# ICS40300-preamp-surfacemount_Rev-D.net
KiCad netlist of a schematic drawn in EAGLE
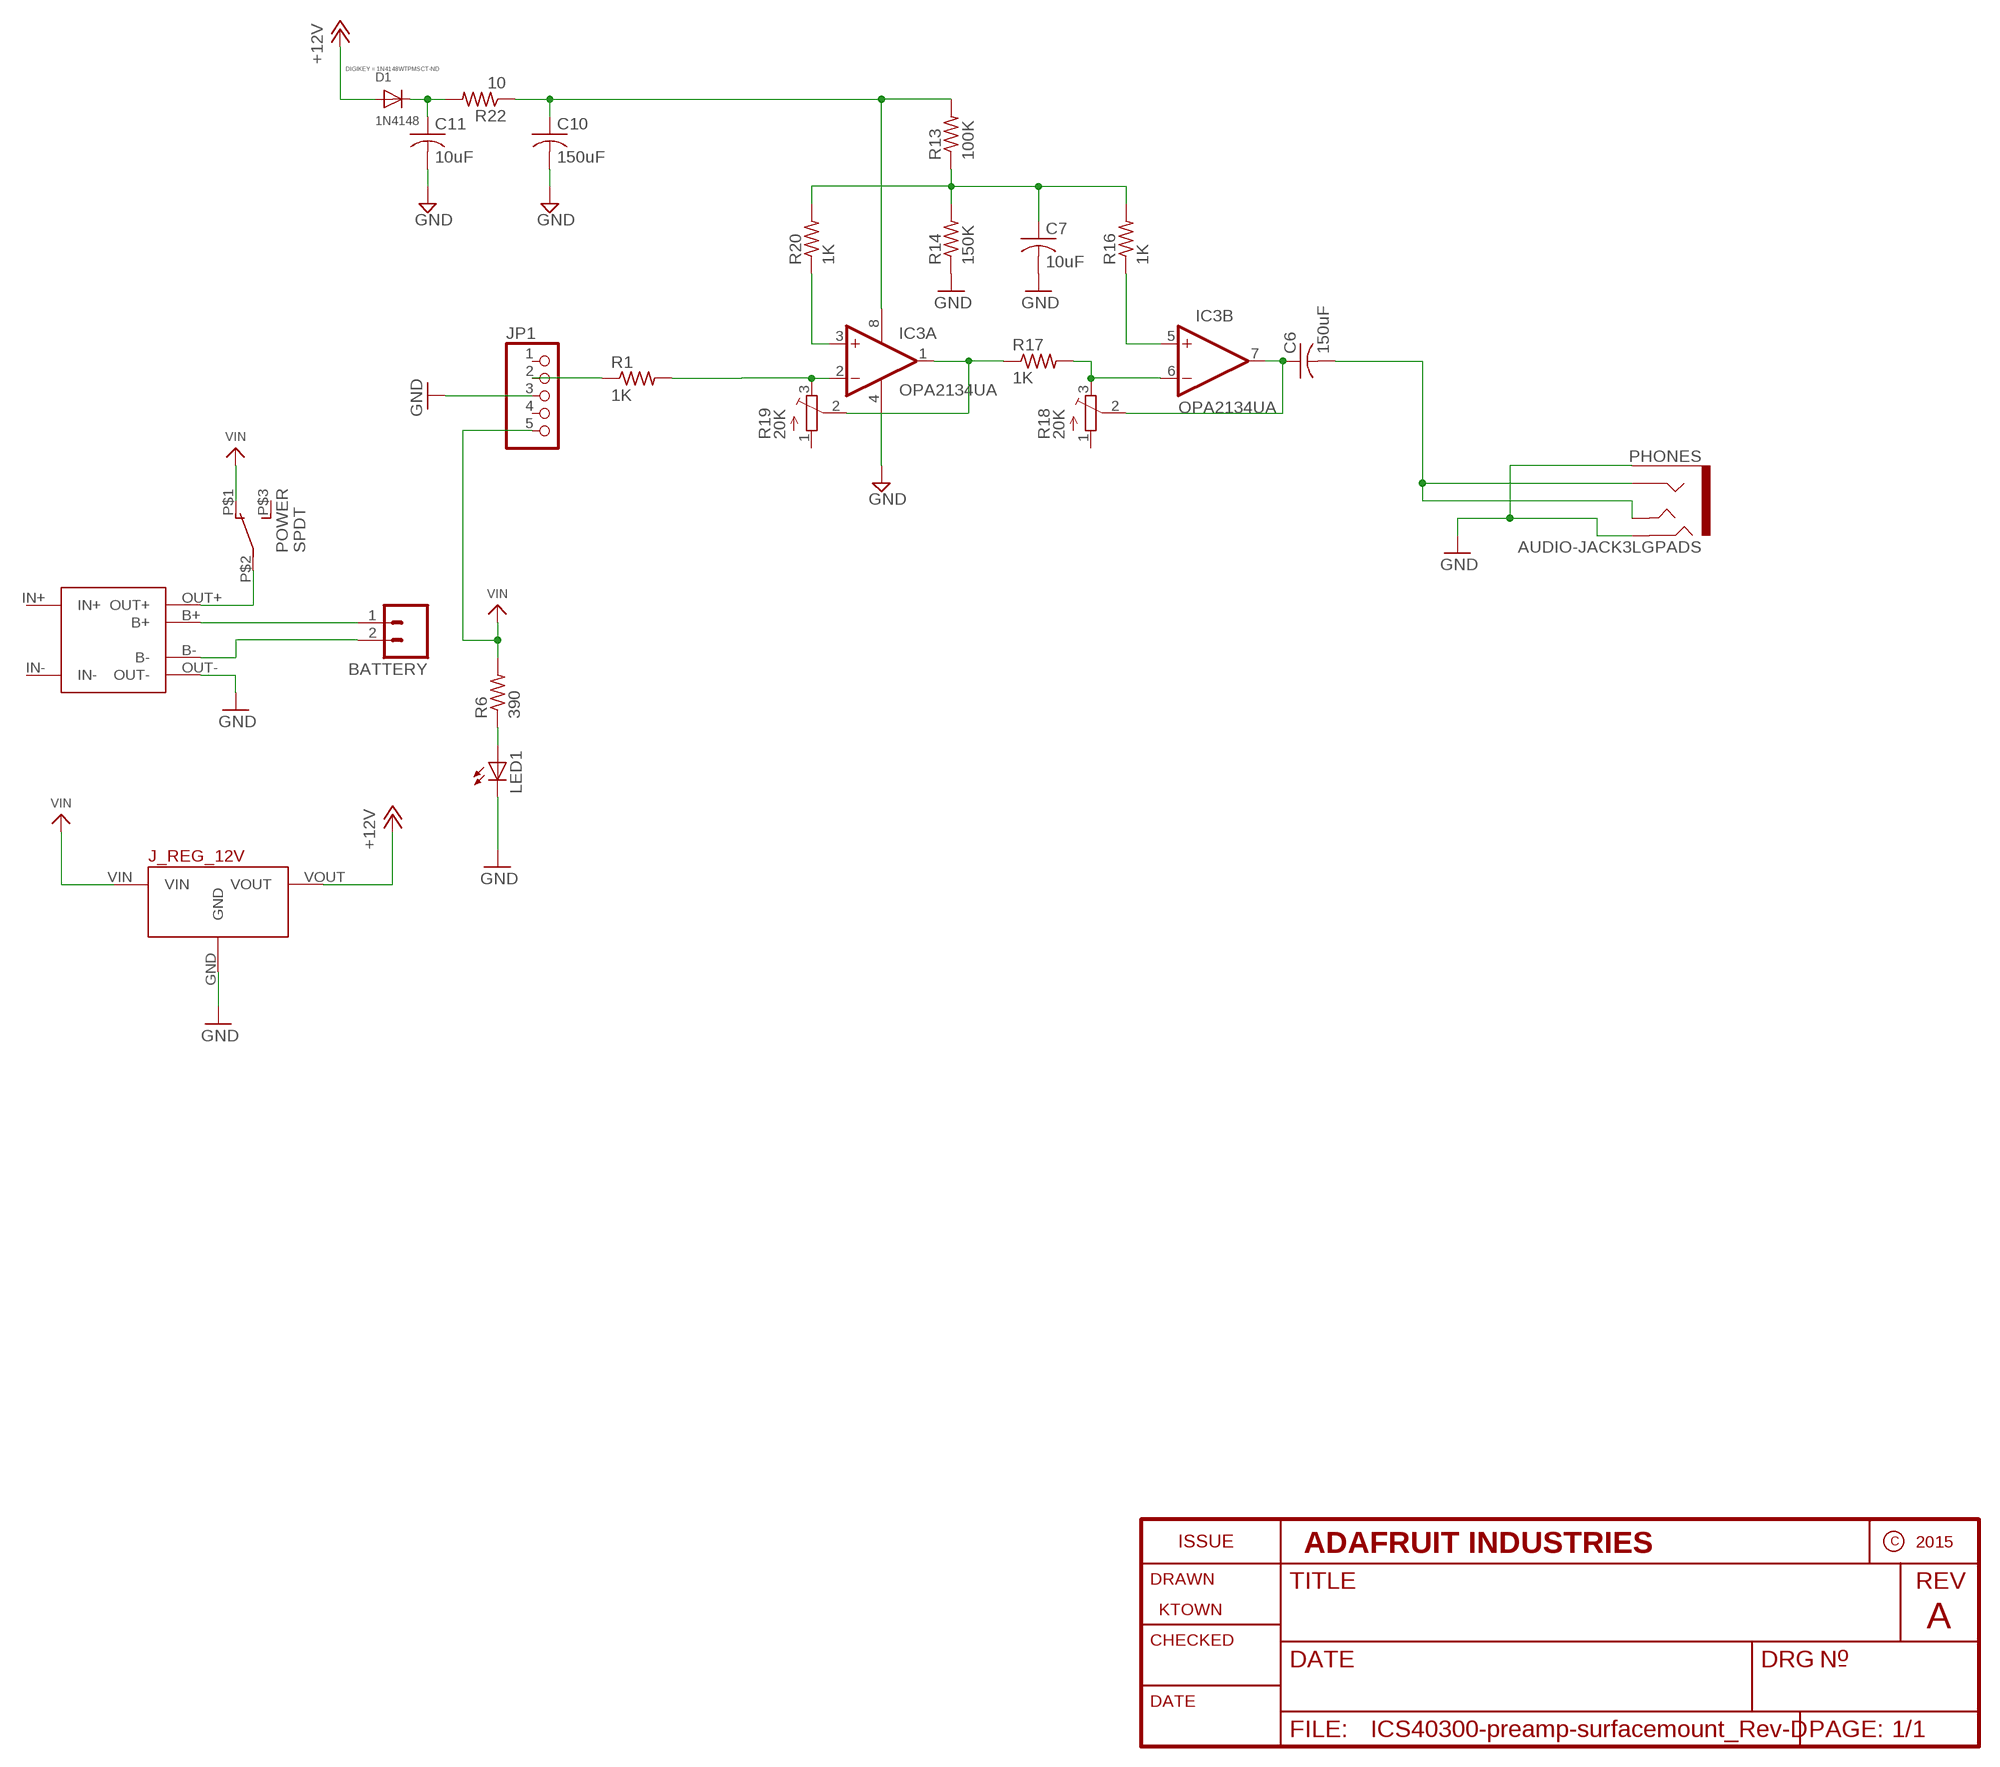
[diagram p0: schematic, sheet 1]

(export (version "E")
  (design (tool "Eeschema 10.0.6"))
  (components
    (comp (ref "BATTERY")
      (value "M02LOCK")
      (footprint "eagle-import:1X02_LOCK")
      (libsource (lib "eagle-import") (part "M02LOCK"))
    )
    (comp (ref "C6")
      (value "150uF")
      (footprint "eagle-import:C3216")
      (libsource (lib "eagle-import") (part "C-USC3216"))
    )
    (comp (ref "C7")
      (value "10uF")
      (footprint "eagle-import:C0805K")
      (libsource (lib "eagle-import") (part "C-USC0805K"))
    )
    (comp (ref "C10")
      (value "150uF")
      (footprint "eagle-import:C3216")
      (libsource (lib "eagle-import") (part "C-USC3216"))
    )
    (comp (ref "C11")
      (value "10uF")
      (footprint "eagle-import:C0805K")
      (libsource (lib "eagle-import") (part "C-USC0805K"))
    )
    (comp (ref "D1")
      (value "1N4148")
      (footprint "eagle-import:SOD-123")
      (fields (field (name "DIGIKEY") "1N4148WTPMSCT-ND"))
      (libsource (lib "eagle-import") (part "DIODESOD-123"))
    )
    (comp (ref "IC3")
      (value "OPA2134UA")
      (footprint "eagle-import:SO08")
      (libsource (lib "eagle-import") (part "OPA2UA134"))
    )
    (comp (ref "JP1")
      (value "HEADER-1X576MIL")
      (footprint "eagle-import:1X05_ROUND_76")
      (libsource (lib "eagle-import") (part "HEADER-1X576MIL"))
    )
    (comp (ref "J_REG_12V")
      (value "POLOLU_VOLTAGE_REGULATORS_3PIN")
      (footprint "eagle-import:POLOLU_5V-12V_STEPUP_U3V12F5-U3V12F12")
      (libsource (lib "eagle-import") (part "POLOLU_VOLTAGE_REGULATORS_3PIN"))
    )
    (comp (ref "LED1")
      (value "LED3MM")
      (footprint "eagle-import:LED3MM")
      (libsource (lib "eagle-import") (part "LED3MM"))
    )
    (comp (ref "PHONES")
      (value "AUDIO-JACK3LGPADS")
      (footprint "eagle-import:AUDIO-JACK-TRRS-SMD")
      (libsource (lib "eagle-import") (part "AUDIO-JACK3LGPADS"))
    )
    (comp (ref "POWER")
      (value "SPDT")
      (footprint "eagle-import:SWITCH_SPDT_CL-SB-12B")
      (libsource (lib "eagle-import") (part "SWITCH_SPDTCL-SB-12B"))
    )
    (comp (ref "R1")
      (value "1K")
      (footprint "eagle-import:R0805")
      (libsource (lib "eagle-import") (part "R-US_R0805"))
    )
    (comp (ref "R6")
      (value "390")
      (footprint "eagle-import:R0805")
      (libsource (lib "eagle-import") (part "R-US_R0805"))
    )
    (comp (ref "R13")
      (value "100K")
      (footprint "eagle-import:R0603")
      (libsource (lib "eagle-import") (part "R-US_R0603"))
    )
    (comp (ref "R14")
      (value "150K")
      (footprint "eagle-import:R0603")
      (libsource (lib "eagle-import") (part "R-US_R0603"))
    )
    (comp (ref "R16")
      (value "1K")
      (footprint "eagle-import:R0603")
      (libsource (lib "eagle-import") (part "R-US_R0603"))
    )
    (comp (ref "R17")
      (value "1K")
      (footprint "eagle-import:R0603")
      (libsource (lib "eagle-import") (part "R-US_R0603"))
    )
    (comp (ref "R18")
      (value "20K")
      (footprint "eagle-import:TC33X")
      (libsource (lib "eagle-import") (part "TRIMPOTTC33X"))
    )
    (comp (ref "R19")
      (value "20K")
      (footprint "eagle-import:TC33X")
      (libsource (lib "eagle-import") (part "TRIMPOTTC33X"))
    )
    (comp (ref "R20")
      (value "1K")
      (footprint "eagle-import:R0603")
      (libsource (lib "eagle-import") (part "R-US_R0603"))
    )
    (comp (ref "R22")
      (value "10")
      (footprint "eagle-import:R0603")
      (libsource (lib "eagle-import") (part "R-US_R0603"))
    )
    (comp (ref "U$1")
      (value "TP4056-MODULETP4056")
      (footprint "eagle-import:TP4056-LITHIUM-PROTECTED-MODULE-MOVED-PAD")
      (libsource (lib "eagle-import") (part "TP4056-MODULETP4056"))
    )
  )
  (nets
    (net (code "1") (name "+12V") (class "Default")
      (node (ref "D1") (pin "A") (pinfunction "A_A") (pintype "passive"))
      (node (ref "J_REG_12V") (pin "VOUT") (pinfunction "VOUT_VOUT") (pintype "bidirectional"))
    )
    (net (code "2") (name "/IN+") (class "Default")
      (node (ref "U$1") (pin "IN+") (pinfunction "IN+_IN+") (pintype "power_in"))
    )
    (net (code "3") (name "/IN-") (class "Default")
      (node (ref "U$1") (pin "IN-") (pinfunction "IN-_IN-") (pintype "power_in"))
    )
    (net (code "4") (name "GND") (class "Default")
      (node (ref "C10") (pin "2") (pinfunction "2_2") (pintype "passive"))
      (node (ref "C11") (pin "2") (pinfunction "2_2") (pintype "passive"))
      (node (ref "C7") (pin "2") (pinfunction "2_2") (pintype "passive"))
      (node (ref "IC3") (pin "4") (pinfunction "V-_4") (pintype "power_in"))
      (node (ref "JP1") (pin "3") (pinfunction "3_3") (pintype "passive"))
      (node (ref "J_REG_12V") (pin "GND") (pinfunction "GND_GND") (pintype "bidirectional"))
      (node (ref "LED1") (pin "K") (pinfunction "C_K") (pintype "passive"))
      (node (ref "PHONES") (pin "EARTH") (pinfunction "EARTH_EARTH") (pintype "bidirectional"))
      (node (ref "PHONES") (pin "RING2") (pinfunction "RING2_RING2") (pintype "bidirectional"))
      (node (ref "R14") (pin "1") (pinfunction "1_1") (pintype "passive"))
      (node (ref "U$1") (pin "OUT-") (pinfunction "OUT-_OUT-") (pintype "power_in"))
    )
    (net (code "5") (name "Net-(BATTERY-Pad1)") (class "Default")
      (node (ref "BATTERY") (pin "1") (pinfunction "1_1") (pintype "passive"))
      (node (ref "U$1") (pin "B+") (pinfunction "B+_B+") (pintype "power_in"))
    )
    (net (code "6") (name "Net-(BATTERY-Pad2)") (class "Default")
      (node (ref "BATTERY") (pin "2") (pinfunction "2_2") (pintype "passive"))
      (node (ref "U$1") (pin "B-") (pinfunction "B-_B-") (pintype "power_in"))
    )
    (net (code "7") (name "Net-(C6-Pad2)") (class "Default")
      (node (ref "C6") (pin "2") (pinfunction "2_2") (pintype "passive"))
      (node (ref "PHONES") (pin "RING1") (pinfunction "RING1_RING1") (pintype "bidirectional"))
      (node (ref "PHONES") (pin "TIP") (pinfunction "TIP_TIP") (pintype "bidirectional"))
    )
    (net (code "8") (name "Net-(C7-Pad1)") (class "Default")
      (node (ref "C7") (pin "1") (pinfunction "1_1") (pintype "passive"))
      (node (ref "R13") (pin "1") (pinfunction "1_1") (pintype "passive"))
      (node (ref "R14") (pin "2") (pinfunction "2_2") (pintype "passive"))
      (node (ref "R16") (pin "2") (pinfunction "2_2") (pintype "passive"))
      (node (ref "R20") (pin "2") (pinfunction "2_2") (pintype "passive"))
    )
    (net (code "9") (name "Net-(C11-Pad1)") (class "Default")
      (node (ref "C11") (pin "1") (pinfunction "1_1") (pintype "passive"))
      (node (ref "D1") (pin "C") (pinfunction "C_C") (pintype "passive"))
      (node (ref "R22") (pin "2") (pinfunction "2_2") (pintype "passive"))
    )
    (net (code "10") (name "Net-(IC3A-+IN)") (class "Default")
      (node (ref "IC3") (pin "3") (pinfunction "+IN_3") (pintype "input"))
      (node (ref "R20") (pin "1") (pinfunction "1_1") (pintype "passive"))
    )
    (net (code "11") (name "Net-(IC3A--IN)") (class "Default")
      (node (ref "IC3") (pin "2") (pinfunction "-IN_2") (pintype "input"))
      (node (ref "R1") (pin "2") (pinfunction "2_2") (pintype "passive"))
      (node (ref "R19") (pin "3") (pinfunction "E_3") (pintype "passive"))
    )
    (net (code "12") (name "Net-(IC3A-OUT)") (class "Default")
      (node (ref "IC3") (pin "1") (pinfunction "OUT_1") (pintype "output"))
      (node (ref "R17") (pin "1") (pinfunction "1_1") (pintype "passive"))
      (node (ref "R19") (pin "2") (pinfunction "S_2") (pintype "passive"))
    )
    (net (code "13") (name "Net-(IC3A-V+)") (class "Default")
      (node (ref "C10") (pin "1") (pinfunction "1_1") (pintype "passive"))
      (node (ref "IC3") (pin "8") (pinfunction "V+_8") (pintype "power_in"))
      (node (ref "R13") (pin "2") (pinfunction "2_2") (pintype "passive"))
      (node (ref "R22") (pin "1") (pinfunction "1_1") (pintype "passive"))
    )
    (net (code "14") (name "Net-(IC3B-+IN)") (class "Default")
      (node (ref "IC3") (pin "5") (pinfunction "+IN_5") (pintype "input"))
      (node (ref "R16") (pin "1") (pinfunction "1_1") (pintype "passive"))
    )
    (net (code "15") (name "Net-(IC3B--IN)") (class "Default")
      (node (ref "IC3") (pin "6") (pinfunction "-IN_6") (pintype "input"))
      (node (ref "R17") (pin "2") (pinfunction "2_2") (pintype "passive"))
      (node (ref "R18") (pin "3") (pinfunction "E_3") (pintype "passive"))
    )
    (net (code "16") (name "Net-(IC3B-OUT)") (class "Default")
      (node (ref "C6") (pin "1") (pinfunction "1_1") (pintype "passive"))
      (node (ref "IC3") (pin "7") (pinfunction "OUT_7") (pintype "output"))
      (node (ref "R18") (pin "2") (pinfunction "S_2") (pintype "passive"))
    )
    (net (code "17") (name "Net-(JP1-Pad2)") (class "Default")
      (node (ref "JP1") (pin "2") (pinfunction "2_2") (pintype "passive"))
      (node (ref "R1") (pin "1") (pinfunction "1_1") (pintype "passive"))
    )
    (net (code "18") (name "Net-(LED1-PadA)") (class "Default")
      (node (ref "LED1") (pin "A") (pinfunction "A_A") (pintype "passive"))
      (node (ref "R6") (pin "1") (pinfunction "1_1") (pintype "passive"))
    )
    (net (code "19") (name "Net-(POWER-2)") (class "Default")
      (node (ref "POWER") (pin "P$2") (pinfunction "2_P$2") (pintype "passive"))
      (node (ref "U$1") (pin "OUT+") (pinfunction "OUT+_OUT+") (pintype "power_in"))
    )
    (net (code "20") (name "VIN") (class "Default")
      (node (ref "JP1") (pin "5") (pinfunction "5_5") (pintype "passive"))
      (node (ref "J_REG_12V") (pin "VIN") (pinfunction "VIN_VIN") (pintype "bidirectional"))
      (node (ref "POWER") (pin "P$1") (pinfunction "1_P$1") (pintype "passive"))
      (node (ref "R6") (pin "2") (pinfunction "2_2") (pintype "passive"))
    )
    (net (code "21") (name "unconnected-(JP1-Pad1)") (class "Default")
      (node (ref "JP1") (pin "1") (pinfunction "1_1") (pintype "passive"))
    )
    (net (code "22") (name "unconnected-(JP1-Pad4)") (class "Default")
      (node (ref "JP1") (pin "4") (pinfunction "4_4") (pintype "passive"))
    )
    (net (code "23") (name "unconnected-(POWER-3-PadP$3)") (class "Default")
      (node (ref "POWER") (pin "P$3") (pinfunction "3_P$3") (pintype "passive"))
    )
    (net (code "24") (name "unconnected-(R18-A-Pad1)") (class "Default")
      (node (ref "R18") (pin "1") (pinfunction "A_1") (pintype "passive"))
    )
    (net (code "25") (name "unconnected-(R19-A-Pad1)") (class "Default")
      (node (ref "R19") (pin "1") (pinfunction "A_1") (pintype "passive"))
    )
  )
)
